# CAN_transceiver.net
KiCad netlist of a schematic drawn in Altium Designer
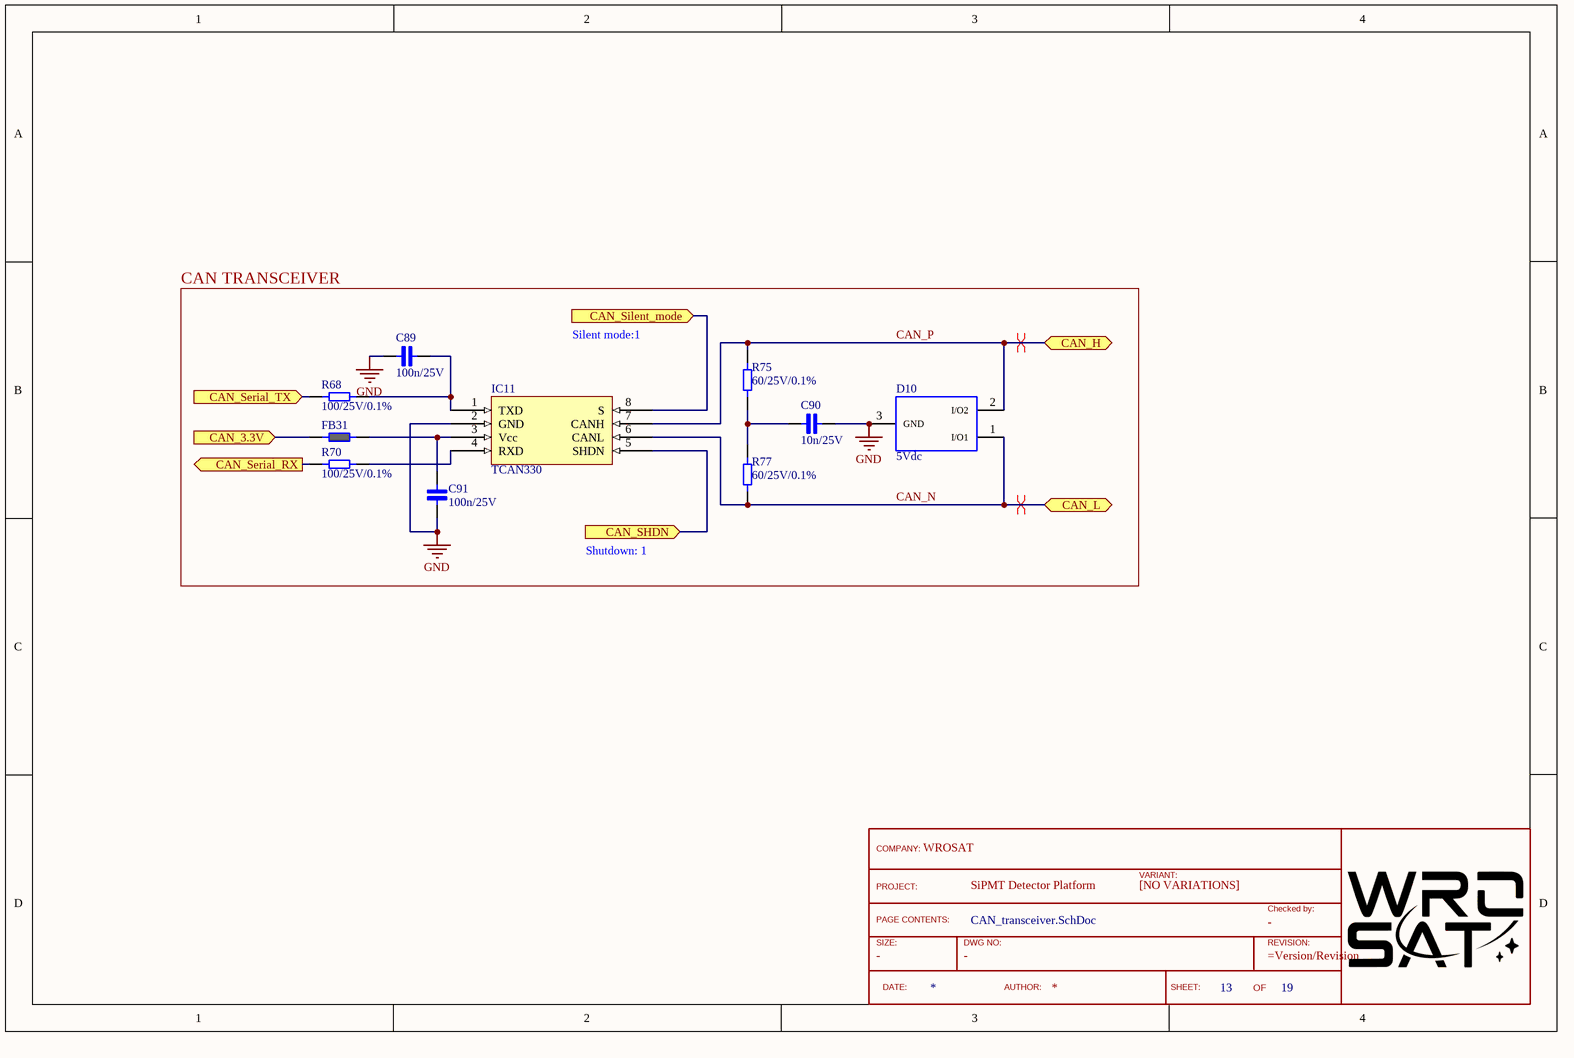
[diagram p0: CAN_transceiver.SchDoc]

(export (version "E")
  (design (tool "Eeschema 10.0.6"))
  (components
    (comp (ref "C89")
      (value "100n/25V")
      (footprint "Cap_0402")
      (description "Ceramic Capacitor 100n / 0402 / 25V / ±5%, Wurth Elektronik MLCC")
      (libsource (lib "Cubesat_lib") (part "Cap_0402_100n"))
    )
    (comp (ref "C90")
      (value "10n/25V")
      (footprint "Cap_0402")
      (description "Ceramic Capacitor 10n / 0402 / 25V / ±5%, Wurth Elektronik MLCC")
      (libsource (lib "Cubesat_lib") (part "Cap_0402_10n"))
    )
    (comp (ref "C91")
      (value "100n/25V")
      (footprint "Cap_0402")
      (description "Ceramic Capacitor 100n / 0402 / 25V / ±5%, Wurth Elektronik MLCC")
      (libsource (lib "") (part "Cap_0402_100n_1"))
    )
    (comp (ref "D10")
      (value "5Vdc")
      (footprint "WE-TVS_SOT23-3L")
      (description "WE-TVS TVS Diode - Standard Series, SOT23-3L, 2Channel, 5Vdc")
      (fields
        (field (name "MANUFACTURER PART NUMBER") "824022")
        (field (name "MANUFACTURER") "Wurth Elektronik")
      )
      (libsource (lib "WE-TVS_standard_tvs") (part "824022"))
    )
    (comp (ref "FB31")
      (value "Ferrite_bead_0402")
      (footprint "FERRITE_0402")
      (description "Ferrite bead, wurth 74269241102")
      (libsource (lib "Cubesat_lib") (part "Ferrite_bead_0402"))
    )
    (comp (ref "IC11")
      (value "TCAN330")
      (footprint "SOIC8")
      (description "CAN transceiver, 3,3V")
      (libsource (lib "Cubesat_lib") (part "TCAN330"))
    )
    (comp (ref "R68")
      (value "100/25V/0.1%")
      (footprint "RES_0402")
      (description "Vishay, thin film resistor 100/25V/0.1%")
      (libsource (lib "Cubesat_lib") (part "Res_0402_100"))
    )
    (comp (ref "R70")
      (value "100/25V/0.1%")
      (footprint "RES_0402")
      (description "Vishay, thin film resistor 100/25V/0.1%")
      (libsource (lib "Cubesat_lib") (part "Res_0402_100"))
    )
    (comp (ref "R75")
      (value "60/25V/0.1%")
      (footprint "RES_1206")
      (description "Vishay, thin film resistor 60/25V/0.1%")
      (libsource (lib "Cubesat_lib") (part "Res_1206_60"))
    )
    (comp (ref "R77")
      (value "60/25V/0.1%")
      (footprint "RES_1206")
      (description "Vishay, thin film resistor 60/25V/0.1%")
      (libsource (lib "Cubesat_lib") (part "Res_1206_60"))
    )
  )
  (nets
    (net (code "1") (name "/CAN_3.3V") (class "Default")
      (node (ref "FB31") (pin "1") (pinfunction "1_1") (pintype "passive"))
    )
    (net (code "2") (name "/CAN_N") (class "Default")
      (node (ref "D10") (pin "1") (pinfunction "I/O1_1") (pintype "passive"))
      (node (ref "IC11") (pin "6") (pinfunction "CANL_6") (pintype "input"))
      (node (ref "R77") (pin "1") (pinfunction "1_1") (pintype "passive"))
    )
    (net (code "3") (name "/CAN_P") (class "Default")
      (node (ref "D10") (pin "2") (pinfunction "I/O2_2") (pintype "passive"))
      (node (ref "IC11") (pin "7") (pinfunction "CANH_7") (pintype "input"))
      (node (ref "R75") (pin "2") (pinfunction "2_2") (pintype "passive"))
    )
    (net (code "4") (name "/CAN_SHDN") (class "Default")
      (node (ref "IC11") (pin "5") (pinfunction "SHDN_5") (pintype "input"))
    )
    (net (code "5") (name "/CAN_Serial_RX") (class "Default")
      (node (ref "R70") (pin "1") (pinfunction "1_1") (pintype "passive"))
    )
    (net (code "6") (name "/CAN_Serial_TX") (class "Default")
      (node (ref "R68") (pin "1") (pinfunction "1_1") (pintype "passive"))
    )
    (net (code "7") (name "/CAN_Silent_mode") (class "Default")
      (node (ref "IC11") (pin "8") (pinfunction "S_8") (pintype "input"))
    )
    (net (code "8") (name "GND") (class "Default")
      (node (ref "C89") (pin "1") (pinfunction "1_1") (pintype "passive"))
      (node (ref "C90") (pin "2") (pinfunction "2_2") (pintype "passive"))
      (node (ref "C91") (pin "1") (pinfunction "1_1") (pintype "passive"))
      (node (ref "D10") (pin "3") (pinfunction "GND_3") (pintype "passive"))
      (node (ref "IC11") (pin "2") (pinfunction "GND_2") (pintype "input"))
    )
    (net (code "9") (name "Net-(C90-Pad1)") (class "Default")
      (node (ref "C90") (pin "1") (pinfunction "1_1") (pintype "passive"))
      (node (ref "R75") (pin "1") (pinfunction "1_1") (pintype "passive"))
      (node (ref "R77") (pin "2") (pinfunction "2_2") (pintype "passive"))
    )
    (net (code "10") (name "Net-(IC11-RXD)") (class "Default")
      (node (ref "IC11") (pin "4") (pinfunction "RXD_4") (pintype "input"))
      (node (ref "R70") (pin "2") (pinfunction "2_2") (pintype "passive"))
    )
    (net (code "11") (name "Net-(IC11-TXD)") (class "Default")
      (node (ref "C89") (pin "2") (pinfunction "2_2") (pintype "passive"))
      (node (ref "IC11") (pin "1") (pinfunction "TXD_1") (pintype "input"))
      (node (ref "R68") (pin "2") (pinfunction "2_2") (pintype "passive"))
    )
    (net (code "12") (name "Net-(IC11-Vcc)") (class "Default")
      (node (ref "C91") (pin "2") (pinfunction "2_2") (pintype "passive"))
      (node (ref "FB31") (pin "2") (pinfunction "2_2") (pintype "passive"))
      (node (ref "IC11") (pin "3") (pinfunction "Vcc_3") (pintype "input"))
    )
  )
)
